# fabbot_v14.net
KiCad netlist of a schematic drawn in EAGLE
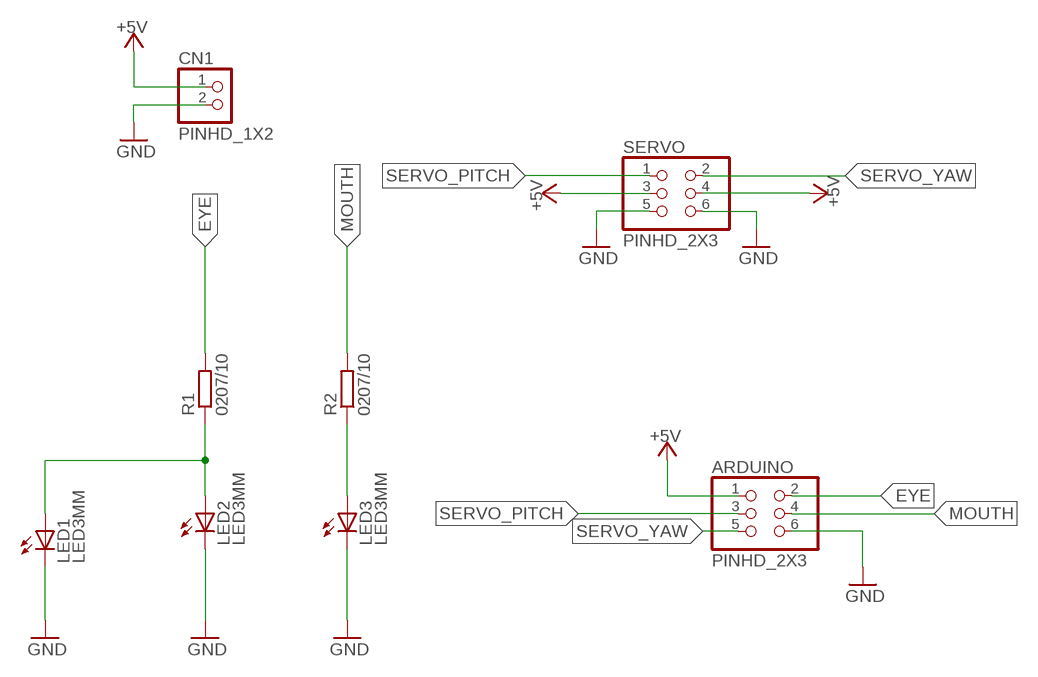
[diagram p0: schematic, sheet 1]

(export (version "E")
  (design (tool "Eeschema 10.0.6"))
  (components
    (comp (ref "ARDUINO")
      (value "PINHD_2X3")
      (footprint "eagle-import:2X03_90")
      (libsource (lib "eagle-import") (part "PINHD_2X3"))
    )
    (comp (ref "CN1")
      (value "PINHD_1X2")
      (footprint "eagle-import:PINHEAD1X2")
      (libsource (lib "eagle-import") (part "PINHD_1X2"))
    )
    (comp (ref "LED1")
      (value "LED3MM")
      (footprint "eagle-import:LED3MM")
      (libsource (lib "eagle-import") (part "LED3MM"))
    )
    (comp (ref "LED2")
      (value "LED3MM")
      (footprint "eagle-import:LED3MM")
      (libsource (lib "eagle-import") (part "LED3MM"))
    )
    (comp (ref "LED3")
      (value "LED3MM")
      (footprint "eagle-import:LED3MM")
      (libsource (lib "eagle-import") (part "LED3MM"))
    )
    (comp (ref "R1")
      (value "0207/10")
      (footprint "eagle-import:0207_10")
      (libsource (lib "eagle-import") (part "0207/10"))
    )
    (comp (ref "R2")
      (value "0207/10")
      (footprint "eagle-import:0207_10")
      (libsource (lib "eagle-import") (part "0207/10"))
    )
    (comp (ref "SERVO")
      (value "PINHD_2X3")
      (footprint "eagle-import:2X03_90")
      (libsource (lib "eagle-import") (part "PINHD_2X3"))
    )
  )
  (nets
    (net (code "1") (name "+5V") (class "Default")
      (node (ref "ARDUINO") (pin "1") (pinfunction "1_1") (pintype "passive"))
      (node (ref "CN1") (pin "1") (pinfunction "1_1") (pintype "passive"))
      (node (ref "SERVO") (pin "3") (pinfunction "3_3") (pintype "passive"))
      (node (ref "SERVO") (pin "4") (pinfunction "4_4") (pintype "passive"))
    )
    (net (code "2") (name "EYE") (class "Default")
      (node (ref "ARDUINO") (pin "2") (pinfunction "2_2") (pintype "passive"))
      (node (ref "R1") (pin "2") (pinfunction "2_2") (pintype "passive"))
    )
    (net (code "3") (name "GND") (class "Default")
      (node (ref "ARDUINO") (pin "6") (pinfunction "6_6") (pintype "passive"))
      (node (ref "CN1") (pin "2") (pinfunction "2_2") (pintype "passive"))
      (node (ref "LED1") (pin "K") (pinfunction "C_K") (pintype "passive"))
      (node (ref "LED2") (pin "K") (pinfunction "C_K") (pintype "passive"))
      (node (ref "LED3") (pin "K") (pinfunction "C_K") (pintype "passive"))
      (node (ref "SERVO") (pin "5") (pinfunction "5_5") (pintype "passive"))
      (node (ref "SERVO") (pin "6") (pinfunction "6_6") (pintype "passive"))
    )
    (net (code "4") (name "MOUTH") (class "Default")
      (node (ref "ARDUINO") (pin "4") (pinfunction "4_4") (pintype "passive"))
      (node (ref "R2") (pin "2") (pinfunction "2_2") (pintype "passive"))
    )
    (net (code "5") (name "Net-(LED1-PadA)") (class "Default")
      (node (ref "LED1") (pin "A") (pinfunction "A_A") (pintype "passive"))
      (node (ref "LED2") (pin "A") (pinfunction "A_A") (pintype "passive"))
      (node (ref "R1") (pin "1") (pinfunction "1_1") (pintype "passive"))
    )
    (net (code "6") (name "Net-(LED3-PadA)") (class "Default")
      (node (ref "LED3") (pin "A") (pinfunction "A_A") (pintype "passive"))
      (node (ref "R2") (pin "1") (pinfunction "1_1") (pintype "passive"))
    )
    (net (code "7") (name "SERVO_PITCH") (class "Default")
      (node (ref "ARDUINO") (pin "3") (pinfunction "3_3") (pintype "passive"))
      (node (ref "SERVO") (pin "1") (pinfunction "1_1") (pintype "passive"))
    )
    (net (code "8") (name "SERVO_YAW") (class "Default")
      (node (ref "ARDUINO") (pin "5") (pinfunction "5_5") (pintype "passive"))
      (node (ref "SERVO") (pin "2") (pinfunction "2_2") (pintype "passive"))
    )
  )
)
